# MCU.net
KiCad netlist of a schematic drawn in Altium Designer
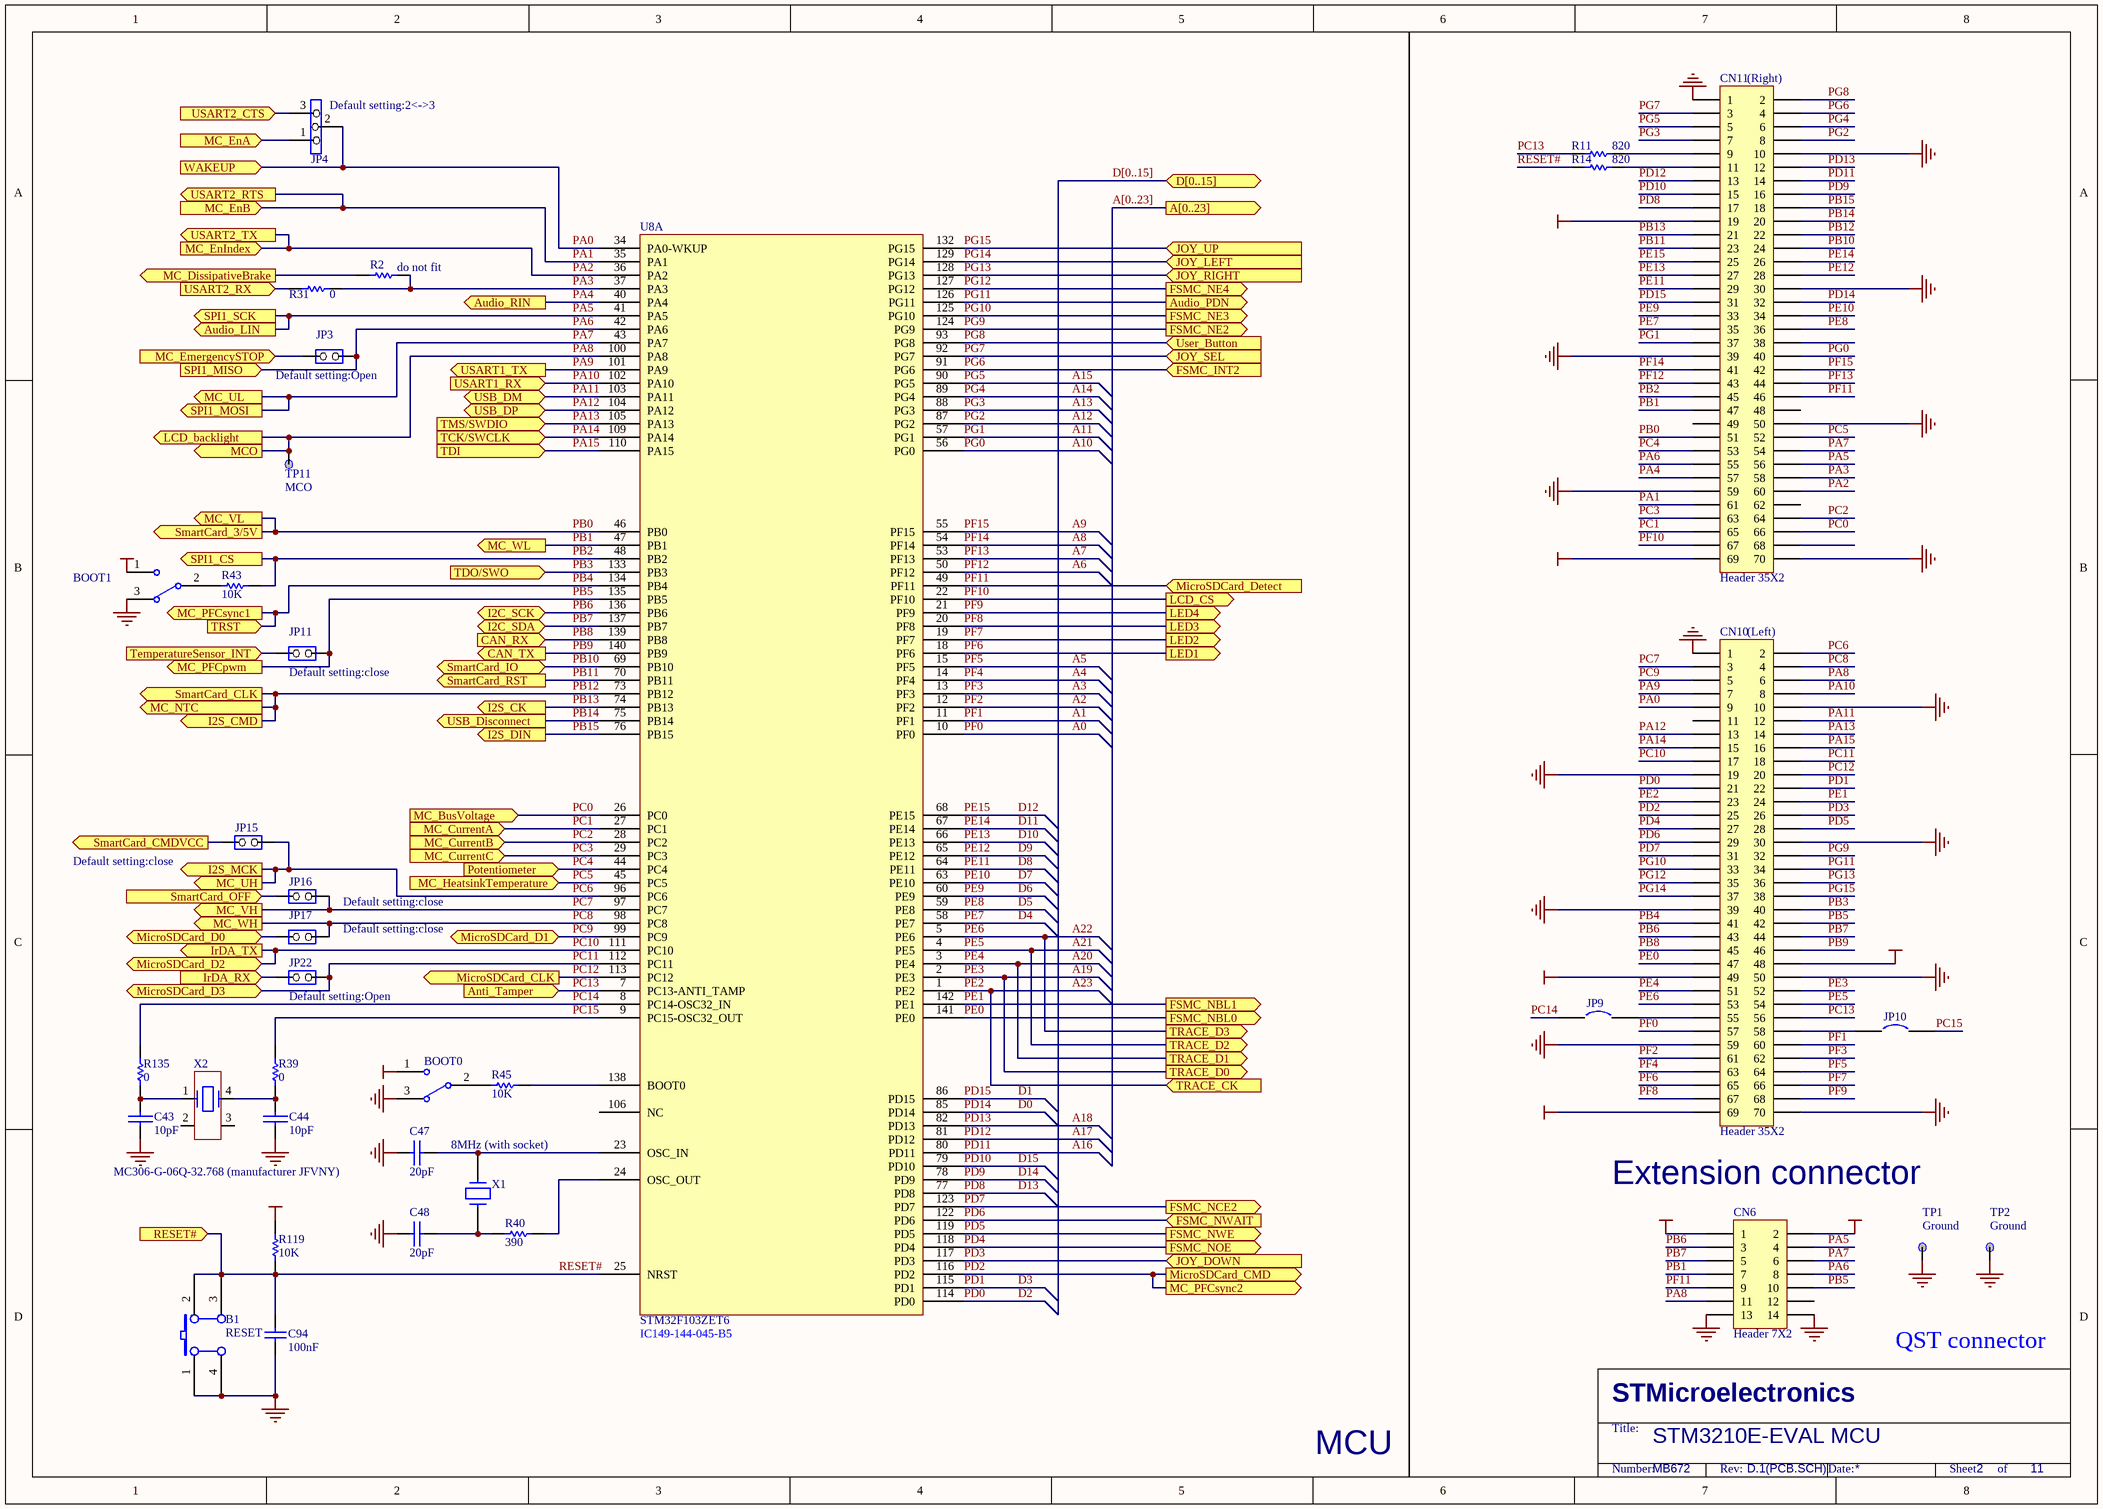
[diagram p0: MCU.SchDoc]

(export (version "E")
  (design (tool "Eeschema 10.0.6"))
  (components
    (comp (ref "B1")
      (value "RESET")
      (footprint "PB10")
      (description "SE PUSHBUTTON")
      (libsource (lib "Documents") (part "SW PUSHBUTTON"))
    )
    (comp (ref "BOOT0")
      (value "~")
      (footprint "SIP3")
      (description "SPDT Subminiature Toggle Switch, Right Angle Mounting, Vertical Actuation")
      (fields (field (name "PUBLISHER") "Altium Limited"))
      (libsource (lib "Miscellaneous Devices") (part "SW-SPDT"))
    )
    (comp (ref "BOOT1")
      (value "~")
      (footprint "SIP3")
      (description "SPDT Subminiature Toggle Switch, Right Angle Mounting, Vertical Actuation")
      (fields (field (name "PUBLISHER") "Altium Limited"))
      (libsource (lib "Miscellaneous Devices") (part "SW-SPDT"))
    )
    (comp (ref "C43")
      (value "10pF")
      (footprint "0603")
      (description "Capacitor")
      (libsource (lib "*") (part "CAP"))
    )
    (comp (ref "C44")
      (value "10pF")
      (footprint "0603")
      (description "Capacitor")
      (libsource (lib "*") (part "CAP"))
    )
    (comp (ref "C47")
      (value "20pF")
      (footprint "0603")
      (description "Capacitor")
      (libsource (lib "") (part "CAP_1"))
    )
    (comp (ref "C48")
      (value "20pF")
      (footprint "0603")
      (description "Capacitor")
      (libsource (lib "") (part "CAP_1"))
    )
    (comp (ref "C94")
      (value "100nF")
      (footprint "0603P")
      (description "Capacitor")
      (fields (field (name "PUBLISHER") "Altium Limited"))
      (libsource (lib "Miscellaneous Devices") (part "CAP"))
    )
    (comp (ref "CN6")
      (value "Header 7X2")
      (footprint "HDR2X7")
      (description "Header, 7-Pin, Dual row")
      (fields (field (name "PUBLISHER") "Altium Limited"))
      (libsource (lib "Miscellaneous Connectors") (part "Header 7X2"))
    )
    (comp (ref "CN10") (value "Header 35X2") (libsource (lib "MB672") (part "Header35X2")))
    (comp (ref "CN11") (value "Header 35X2") (libsource (lib "MB672") (part "Header35X2")))
    (comp (ref "JP3") (value "~") (footprint "SIP2") (libsource (lib "*") (part "JP2")))
    (comp (ref "JP4") (value "~") (footprint "SIP3") (libsource (lib "STR910_SCHLIB") (part "Jumper3")))
    (comp (ref "JP9")
      (value "~")
      (footprint "SPST-2")
      (description "Circuit Breaker")
      (fields (field (name "PUBLISHER") "Altium Limited"))
      (libsource (lib "Miscellaneous Devices") (part "Circuit Breaker"))
    )
    (comp (ref "JP10")
      (value "~")
      (footprint "SPST-2")
      (description "Circuit Breaker")
      (fields (field (name "PUBLISHER") "Altium Limited"))
      (libsource (lib "Miscellaneous Devices") (part "Circuit Breaker"))
    )
    (comp (ref "JP11") (value "~") (footprint "SIP2") (libsource (lib "*") (part "JP2")))
    (comp (ref "JP15") (value "~") (footprint "SIP2") (libsource (lib "*") (part "JP2")))
    (comp (ref "JP16") (value "~") (footprint "SIP2") (libsource (lib "*") (part "JP2")))
    (comp (ref "JP17") (value "~") (footprint "SIP2") (libsource (lib "*") (part "JP2")))
    (comp (ref "JP22") (value "~") (footprint "SIP2") (libsource (lib "*") (part "JP2")))
    (comp (ref "R2")
      (value "do not fit")
      (description "Resistor")
      (fields (field (name "PUBLISHER") "Altium Limited"))
      (libsource (lib "Miscellaneous Devices") (part "res1"))
    )
    (comp (ref "R11")
      (value "820")
      (description "Resistor")
      (fields (field (name "PUBLISHER") "Altium Limited"))
      (libsource (lib "Miscellaneous Devices") (part "Res1"))
    )
    (comp (ref "R14")
      (value "820")
      (description "Resistor")
      (fields (field (name "PUBLISHER") "Altium Limited"))
      (libsource (lib "Miscellaneous Devices") (part "Res1"))
    )
    (comp (ref "R31")
      (value "0")
      (description "Resistor")
      (fields (field (name "PUBLISHER") "Altium Limited"))
      (libsource (lib "Miscellaneous Devices") (part "res1"))
    )
    (comp (ref "R39")
      (value "0")
      (description "Resistor")
      (fields (field (name "PUBLISHER") "Altium Limited"))
      (libsource (lib "Miscellaneous Devices") (part "Res1"))
    )
    (comp (ref "R40")
      (value "390")
      (description "Resistor")
      (fields (field (name "PUBLISHER") "Altium Limited"))
      (libsource (lib "Miscellaneous Devices") (part "Res1"))
    )
    (comp (ref "R43")
      (value "10K")
      (description "Resistor")
      (fields (field (name "PUBLISHER") "Altium Limited"))
      (libsource (lib "Miscellaneous Devices") (part "res1"))
    )
    (comp (ref "R45")
      (value "10K")
      (description "Resistor")
      (fields (field (name "PUBLISHER") "Altium Limited"))
      (libsource (lib "Miscellaneous Devices") (part "res1"))
    )
    (comp (ref "R119")
      (value "10K")
      (footprint "0603")
      (description "Resistor")
      (fields (field (name "PUBLISHER") "Altium Limited"))
      (libsource (lib "Miscellaneous Devices") (part "res1"))
    )
    (comp (ref "R135")
      (value "0")
      (description "Resistor")
      (fields (field (name "PUBLISHER") "Altium Limited"))
      (libsource (lib "Miscellaneous Devices") (part "Res1"))
    )
    (comp (ref "TP1") (value "Ground") (footprint "TP") (libsource (lib "*") (part "TP")))
    (comp (ref "TP2") (value "Ground") (footprint "TP") (libsource (lib "*") (part "TP")))
    (comp (ref "TP11") (value "MCO") (footprint "TP") (libsource (lib "") (part "TP_1")))
    (comp (ref "U8") (value "STM32F103ZET6") (libsource (lib "MB672") (part "BigPiranha_new")))
    (comp (ref "X1")
      (value "8MHz (with socket)")
      (footprint "XTAL1")
      (description "Crystal")
      (libsource (lib "*") (part "CRYSTAL"))
    )
    (comp (ref "X2")
      (value "MC306-G-06Q-32.768 (manufacturer JFVNY)")
      (footprint "SM8")
      (libsource (lib "*") (part "MC306"))
    )
  )
  (nets
    (net (code "1") (name "+3V3") (class "Default")
      (node (ref "BOOT0") (pin "1") (pintype "passive"))
      (node (ref "BOOT1") (pin "1") (pintype "passive"))
      (node (ref "CN10") (pin "48") (pinfunction "48_48") (pintype "passive"))
      (node (ref "CN10") (pin "69") (pinfunction "69_69") (pintype "passive"))
      (node (ref "CN11") (pin "69") (pinfunction "69_69") (pintype "passive"))
      (node (ref "R119") (pin "2") (pinfunction "2_2") (pintype "passive"))
    )
    (net (code "2") (name "+5V") (class "Default")
      (node (ref "CN6") (pin "1") (pinfunction "1_1") (pintype "passive"))
      (node (ref "CN6") (pin "2") (pinfunction "2_2") (pintype "passive"))
    )
    (net (code "3") (name "/A0") (class "Default")
      (node (ref "CN10") (pin "57") (pinfunction "57_57") (pintype "passive"))
      (node (ref "U8") (pin "10") (pinfunction "PF0_10") (pintype "passive"))
    )
    (net (code "4") (name "/A1") (class "Default")
      (node (ref "CN10") (pin "60") (pinfunction "60_60") (pintype "passive"))
      (node (ref "U8") (pin "11") (pinfunction "PF1_11") (pintype "passive"))
    )
    (net (code "5") (name "/A2") (class "Default")
      (node (ref "CN10") (pin "61") (pinfunction "61_61") (pintype "passive"))
      (node (ref "U8") (pin "12") (pinfunction "PF2_12") (pintype "passive"))
    )
    (net (code "6") (name "/A3") (class "Default")
      (node (ref "CN10") (pin "62") (pinfunction "62_62") (pintype "passive"))
      (node (ref "U8") (pin "13") (pinfunction "PF3_13") (pintype "passive"))
    )
    (net (code "7") (name "/A4") (class "Default")
      (node (ref "CN10") (pin "63") (pinfunction "63_63") (pintype "passive"))
      (node (ref "U8") (pin "14") (pinfunction "PF4_14") (pintype "passive"))
    )
    (net (code "8") (name "/A5") (class "Default")
      (node (ref "CN10") (pin "64") (pinfunction "64_64") (pintype "passive"))
      (node (ref "U8") (pin "15") (pinfunction "PF5_15") (pintype "passive"))
    )
    (net (code "9") (name "/A6") (class "Default")
      (node (ref "CN11") (pin "43") (pinfunction "43_43") (pintype "passive"))
      (node (ref "U8") (pin "50") (pinfunction "PF12_50") (pintype "passive"))
    )
    (net (code "10") (name "/A7") (class "Default")
      (node (ref "CN11") (pin "44") (pinfunction "44_44") (pintype "passive"))
      (node (ref "U8") (pin "53") (pinfunction "PF13_53") (pintype "passive"))
    )
    (net (code "11") (name "/A8") (class "Default")
      (node (ref "CN11") (pin "41") (pinfunction "41_41") (pintype "passive"))
      (node (ref "U8") (pin "54") (pinfunction "PF14_54") (pintype "passive"))
    )
    (net (code "12") (name "/A9") (class "Default")
      (node (ref "CN11") (pin "42") (pinfunction "42_42") (pintype "passive"))
      (node (ref "U8") (pin "55") (pinfunction "PF15_55") (pintype "passive"))
    )
    (net (code "13") (name "/A10") (class "Default")
      (node (ref "CN11") (pin "40") (pinfunction "40_40") (pintype "passive"))
      (node (ref "U8") (pin "56") (pinfunction "PG0_56") (pintype "passive"))
    )
    (net (code "14") (name "/A11") (class "Default")
      (node (ref "CN11") (pin "37") (pinfunction "37_37") (pintype "passive"))
      (node (ref "U8") (pin "57") (pinfunction "PG1_57") (pintype "passive"))
    )
    (net (code "15") (name "/A12") (class "Default")
      (node (ref "CN11") (pin "8") (pinfunction "8_8") (pintype "passive"))
      (node (ref "U8") (pin "87") (pinfunction "PG2_87") (pintype "passive"))
    )
    (net (code "16") (name "/A13") (class "Default")
      (node (ref "CN11") (pin "7") (pinfunction "7_7") (pintype "passive"))
      (node (ref "U8") (pin "88") (pinfunction "PG3_88") (pintype "passive"))
    )
    (net (code "17") (name "/A14") (class "Default")
      (node (ref "CN11") (pin "6") (pinfunction "6_6") (pintype "passive"))
      (node (ref "U8") (pin "89") (pinfunction "PG4_89") (pintype "passive"))
    )
    (net (code "18") (name "/A15") (class "Default")
      (node (ref "CN11") (pin "5") (pinfunction "5_5") (pintype "passive"))
      (node (ref "U8") (pin "90") (pinfunction "PG5_90") (pintype "passive"))
    )
    (net (code "19") (name "/A16") (class "Default")
      (node (ref "CN11") (pin "14") (pinfunction "14_14") (pintype "passive"))
      (node (ref "U8") (pin "80") (pinfunction "PD11_80") (pintype "passive"))
    )
    (net (code "20") (name "/A17") (class "Default")
      (node (ref "CN11") (pin "13") (pinfunction "13_13") (pintype "passive"))
      (node (ref "U8") (pin "81") (pinfunction "PD12_81") (pintype "passive"))
    )
    (net (code "21") (name "/A18") (class "Default")
      (node (ref "CN11") (pin "12") (pinfunction "12_12") (pintype "passive"))
      (node (ref "U8") (pin "82") (pinfunction "PD13_82") (pintype "passive"))
    )
    (net (code "22") (name "/A19") (class "Default")
      (node (ref "CN10") (pin "52") (pinfunction "52_52") (pintype "passive"))
      (node (ref "U8") (pin "2") (pinfunction "PE3_2") (pintype "passive"))
    )
    (net (code "23") (name "/A20") (class "Default")
      (node (ref "CN10") (pin "51") (pinfunction "51_51") (pintype "passive"))
      (node (ref "U8") (pin "3") (pinfunction "PE4_3") (pintype "passive"))
    )
    (net (code "24") (name "/A21") (class "Default")
      (node (ref "CN10") (pin "54") (pinfunction "54_54") (pintype "passive"))
      (node (ref "U8") (pin "4") (pinfunction "PE5_4") (pintype "passive"))
    )
    (net (code "25") (name "/A22") (class "Default")
      (node (ref "CN10") (pin "53") (pinfunction "53_53") (pintype "passive"))
      (node (ref "U8") (pin "5") (pinfunction "PE6_5") (pintype "passive"))
    )
    (net (code "26") (name "/A23") (class "Default")
      (node (ref "CN10") (pin "23") (pinfunction "23_23") (pintype "passive"))
      (node (ref "U8") (pin "1") (pinfunction "PE2_1") (pintype "passive"))
    )
    (net (code "28") (name "/D0") (class "Default")
      (node (ref "CN11") (pin "32") (pinfunction "32_32") (pintype "passive"))
      (node (ref "U8") (pin "85") (pinfunction "PD14_85") (pintype "passive"))
    )
    (net (code "29") (name "/D1") (class "Default")
      (node (ref "CN11") (pin "31") (pinfunction "31_31") (pintype "passive"))
      (node (ref "U8") (pin "86") (pinfunction "PD15_86") (pintype "passive"))
    )
    (net (code "30") (name "/D2") (class "Default")
      (node (ref "CN10") (pin "21") (pinfunction "21_21") (pintype "passive"))
      (node (ref "U8") (pin "114") (pinfunction "PD0_114") (pintype "passive"))
    )
    (net (code "31") (name "/D3") (class "Default")
      (node (ref "CN10") (pin "22") (pinfunction "22_22") (pintype "passive"))
      (node (ref "U8") (pin "115") (pinfunction "PD1_115") (pintype "passive"))
    )
    (net (code "32") (name "/D4") (class "Default")
      (node (ref "CN11") (pin "35") (pinfunction "35_35") (pintype "passive"))
      (node (ref "U8") (pin "58") (pinfunction "PE7_58") (pintype "passive"))
    )
    (net (code "33") (name "/D5") (class "Default")
      (node (ref "CN11") (pin "36") (pinfunction "36_36") (pintype "passive"))
      (node (ref "U8") (pin "59") (pinfunction "PE8_59") (pintype "passive"))
    )
    (net (code "34") (name "/D6") (class "Default")
      (node (ref "CN11") (pin "33") (pinfunction "33_33") (pintype "passive"))
      (node (ref "U8") (pin "60") (pinfunction "PE9_60") (pintype "passive"))
    )
    (net (code "35") (name "/D7") (class "Default")
      (node (ref "CN11") (pin "34") (pinfunction "34_34") (pintype "passive"))
      (node (ref "U8") (pin "63") (pinfunction "PE10_63") (pintype "passive"))
    )
    (net (code "36") (name "/D8") (class "Default")
      (node (ref "CN11") (pin "29") (pinfunction "29_29") (pintype "passive"))
      (node (ref "U8") (pin "64") (pinfunction "PE11_64") (pintype "passive"))
    )
    (net (code "37") (name "/D9") (class "Default")
      (node (ref "CN11") (pin "28") (pinfunction "28_28") (pintype "passive"))
      (node (ref "U8") (pin "65") (pinfunction "PE12_65") (pintype "passive"))
    )
    (net (code "38") (name "/D10") (class "Default")
      (node (ref "CN11") (pin "27") (pinfunction "27_27") (pintype "passive"))
      (node (ref "U8") (pin "66") (pinfunction "PE13_66") (pintype "passive"))
    )
    (net (code "39") (name "/D11") (class "Default")
      (node (ref "CN11") (pin "26") (pinfunction "26_26") (pintype "passive"))
      (node (ref "U8") (pin "67") (pinfunction "PE14_67") (pintype "passive"))
    )
    (net (code "40") (name "/D12") (class "Default")
      (node (ref "CN11") (pin "25") (pinfunction "25_25") (pintype "passive"))
      (node (ref "U8") (pin "68") (pinfunction "PE15_68") (pintype "passive"))
    )
    (net (code "41") (name "/D13") (class "Default")
      (node (ref "CN11") (pin "17") (pinfunction "17_17") (pintype "passive"))
      (node (ref "U8") (pin "77") (pinfunction "PD8_77") (pintype "passive"))
    )
    (net (code "42") (name "/D14") (class "Default")
      (node (ref "CN11") (pin "16") (pinfunction "16_16") (pintype "passive"))
      (node (ref "U8") (pin "78") (pinfunction "PD9_78") (pintype "passive"))
    )
    (net (code "43") (name "/D15") (class "Default")
      (node (ref "CN11") (pin "15") (pinfunction "15_15") (pintype "passive"))
      (node (ref "U8") (pin "79") (pinfunction "PD10_79") (pintype "passive"))
    )
    (net (code "45") (name "/IrDA_RX") (class "Default")
      (node (ref "JP22") (pin "2") (pinfunction "NO_2") (pintype "passive"))
    )
    (net (code "46") (name "/MC_DissipativeBrake") (class "Default")
      (node (ref "R2") (pin "2") (pinfunction "2_2") (pintype "passive"))
    )
    (net (code "47") (name "/MC_EmergencySTOP") (class "Default")
      (node (ref "JP3") (pin "2") (pinfunction "NO_2") (pintype "passive"))
    )
    (net (code "48") (name "/MC_EnA") (class "Default") (node (ref "JP4") (pin "1") (pintype "passive")))
    (net (code "49") (name "/MicroSDCard_D0") (class "Default")
      (node (ref "JP17") (pin "2") (pinfunction "NO_2") (pintype "passive"))
    )
    (net (code "50") (name "/PA0") (class "Default")
      (node (ref "CN10") (pin "9") (pinfunction "9_9") (pintype "passive"))
      (node (ref "JP4") (pin "2") (pintype "passive"))
      (node (ref "U8") (pin "34") (pinfunction "PA0-WKUP_34") (pintype "passive"))
    )
    (net (code "51") (name "/PA1") (class "Default")
      (node (ref "CN11") (pin "61") (pinfunction "61_61") (pintype "passive"))
      (node (ref "U8") (pin "35") (pinfunction "PA1_35") (pintype "passive"))
    )
    (net (code "52") (name "/PA2") (class "Default")
      (node (ref "CN11") (pin "60") (pinfunction "60_60") (pintype "passive"))
      (node (ref "U8") (pin "36") (pinfunction "PA2_36") (pintype "passive"))
    )
    (net (code "53") (name "/PA3") (class "Default")
      (node (ref "CN11") (pin "58") (pinfunction "58_58") (pintype "passive"))
      (node (ref "R2") (pin "1") (pinfunction "1_1") (pintype "passive"))
      (node (ref "R31") (pin "1") (pinfunction "1_1") (pintype "passive"))
      (node (ref "U8") (pin "37") (pinfunction "PA3_37") (pintype "passive"))
    )
    (net (code "54") (name "/PA4") (class "Default")
      (node (ref "CN11") (pin "57") (pinfunction "57_57") (pintype "passive"))
      (node (ref "U8") (pin "40") (pinfunction "PA4_40") (pintype "passive"))
    )
    (net (code "55") (name "/PA5") (class "Default")
      (node (ref "CN11") (pin "56") (pinfunction "56_56") (pintype "passive"))
      (node (ref "CN6") (pin "4") (pinfunction "4_4") (pintype "passive"))
      (node (ref "U8") (pin "41") (pinfunction "PA5_41") (pintype "passive"))
    )
    (net (code "56") (name "/PA6") (class "Default")
      (node (ref "CN11") (pin "55") (pinfunction "55_55") (pintype "passive"))
      (node (ref "CN6") (pin "8") (pinfunction "8_8") (pintype "passive"))
      (node (ref "JP3") (pin "1") (pinfunction "COMMON_1") (pintype "passive"))
      (node (ref "U8") (pin "42") (pinfunction "PA6_42") (pintype "passive"))
    )
    (net (code "57") (name "/PA7") (class "Default")
      (node (ref "CN11") (pin "54") (pinfunction "54_54") (pintype "passive"))
      (node (ref "CN6") (pin "6") (pinfunction "6_6") (pintype "passive"))
      (node (ref "U8") (pin "43") (pinfunction "PA7_43") (pintype "passive"))
    )
    (net (code "58") (name "/PA8") (class "Default")
      (node (ref "CN10") (pin "6") (pinfunction "6_6") (pintype "passive"))
      (node (ref "CN6") (pin "11") (pinfunction "11_11") (pintype "passive"))
      (node (ref "TP11") (pin "1") (pinfunction "1_1") (pintype "passive"))
      (node (ref "U8") (pin "100") (pinfunction "PA8_100") (pintype "passive"))
    )
    (net (code "59") (name "/PA9") (class "Default")
      (node (ref "CN10") (pin "7") (pinfunction "7_7") (pintype "passive"))
      (node (ref "U8") (pin "101") (pinfunction "PA9_101") (pintype "passive"))
    )
    (net (code "60") (name "/PA10") (class "Default")
      (node (ref "CN10") (pin "8") (pinfunction "8_8") (pintype "passive"))
      (node (ref "U8") (pin "102") (pinfunction "PA10_102") (pintype "passive"))
    )
    (net (code "61") (name "/PA11") (class "Default")
      (node (ref "CN10") (pin "12") (pinfunction "12_12") (pintype "passive"))
      (node (ref "U8") (pin "103") (pinfunction "PA11_103") (pintype "passive"))
    )
    (net (code "62") (name "/PA12") (class "Default")
      (node (ref "CN10") (pin "13") (pinfunction "13_13") (pintype "passive"))
      (node (ref "U8") (pin "104") (pinfunction "PA12_104") (pintype "passive"))
    )
    (net (code "63") (name "/PA13") (class "Default")
      (node (ref "CN10") (pin "14") (pinfunction "14_14") (pintype "passive"))
      (node (ref "U8") (pin "105") (pinfunction "PA13_105") (pintype "passive"))
    )
    (net (code "64") (name "/PA14") (class "Default")
      (node (ref "CN10") (pin "15") (pinfunction "15_15") (pintype "passive"))
      (node (ref "U8") (pin "109") (pinfunction "PA14_109") (pintype "passive"))
    )
    (net (code "65") (name "/PA15") (class "Default")
      (node (ref "CN10") (pin "16") (pinfunction "16_16") (pintype "passive"))
      (node (ref "U8") (pin "110") (pinfunction "PA15_110") (pintype "passive"))
    )
    (net (code "66") (name "/PB0") (class "Default")
      (node (ref "CN11") (pin "51") (pinfunction "51_51") (pintype "passive"))
      (node (ref "U8") (pin "46") (pinfunction "PB0_46") (pintype "passive"))
    )
    (net (code "67") (name "/PB1") (class "Default")
      (node (ref "CN11") (pin "47") (pinfunction "47_47") (pintype "passive"))
      (node (ref "CN6") (pin "7") (pinfunction "7_7") (pintype "passive"))
      (node (ref "U8") (pin "47") (pinfunction "PB1_47") (pintype "passive"))
    )
    (net (code "68") (name "/PB2") (class "Default")
      (node (ref "CN11") (pin "45") (pinfunction "45_45") (pintype "passive"))
      (node (ref "R43") (pin "1") (pinfunction "1_1") (pintype "passive"))
      (node (ref "U8") (pin "48") (pinfunction "PB2_48") (pintype "passive"))
    )
    (net (code "69") (name "/PB3") (class "Default")
      (node (ref "CN10") (pin "40") (pinfunction "40_40") (pintype "passive"))
      (node (ref "U8") (pin "133") (pinfunction "PB3_133") (pintype "passive"))
    )
    (net (code "70") (name "/PB4") (class "Default")
      (node (ref "CN10") (pin "41") (pinfunction "41_41") (pintype "passive"))
      (node (ref "U8") (pin "134") (pinfunction "PB4_134") (pintype "passive"))
    )
    (net (code "71") (name "/PB5") (class "Default")
      (node (ref "CN10") (pin "42") (pinfunction "42_42") (pintype "passive"))
      (node (ref "CN6") (pin "10") (pinfunction "10_10") (pintype "passive"))
      (node (ref "JP11") (pin "1") (pinfunction "COMMON_1") (pintype "passive"))
      (node (ref "U8") (pin "135") (pinfunction "PB5_135") (pintype "passive"))
    )
    (net (code "72") (name "/PB6") (class "Default")
      (node (ref "CN10") (pin "43") (pinfunction "43_43") (pintype "passive"))
      (node (ref "CN6") (pin "3") (pinfunction "3_3") (pintype "passive"))
      (node (ref "U8") (pin "136") (pinfunction "PB6_136") (pintype "passive"))
    )
    (net (code "73") (name "/PB7") (class "Default")
      (node (ref "CN10") (pin "44") (pinfunction "44_44") (pintype "passive"))
      (node (ref "CN6") (pin "5") (pinfunction "5_5") (pintype "passive"))
      (node (ref "U8") (pin "137") (pinfunction "PB7_137") (pintype "passive"))
    )
    (net (code "74") (name "/PB8") (class "Default")
      (node (ref "CN10") (pin "45") (pinfunction "45_45") (pintype "passive"))
      (node (ref "U8") (pin "139") (pinfunction "PB8_139") (pintype "passive"))
    )
    (net (code "75") (name "/PB9") (class "Default")
      (node (ref "CN10") (pin "46") (pinfunction "46_46") (pintype "passive"))
      (node (ref "U8") (pin "140") (pinfunction "PB9_140") (pintype "passive"))
    )
    (net (code "76") (name "/PB10") (class "Default")
      (node (ref "CN11") (pin "24") (pinfunction "24_24") (pintype "passive"))
      (node (ref "U8") (pin "69") (pinfunction "PB10_69") (pintype "passive"))
    )
    (net (code "77") (name "/PB11") (class "Default")
      (node (ref "CN11") (pin "23") (pinfunction "23_23") (pintype "passive"))
      (node (ref "U8") (pin "70") (pinfunction "PB11_70") (pintype "passive"))
    )
    (net (code "78") (name "/PB12") (class "Default")
      (node (ref "CN11") (pin "22") (pinfunction "22_22") (pintype "passive"))
      (node (ref "U8") (pin "73") (pinfunction "PB12_73") (pintype "passive"))
    )
    (net (code "79") (name "/PB13") (class "Default")
      (node (ref "CN11") (pin "21") (pinfunction "21_21") (pintype "passive"))
      (node (ref "U8") (pin "74") (pinfunction "PB13_74") (pintype "passive"))
    )
    (net (code "80") (name "/PB14") (class "Default")
      (node (ref "CN11") (pin "20") (pinfunction "20_20") (pintype "passive"))
      (node (ref "U8") (pin "75") (pinfunction "PB14_75") (pintype "passive"))
    )
    (net (code "81") (name "/PB15") (class "Default")
      (node (ref "CN11") (pin "18") (pinfunction "18_18") (pintype "passive"))
      (node (ref "U8") (pin "76") (pinfunction "PB15_76") (pintype "passive"))
    )
    (net (code "82") (name "/PC0") (class "Default")
      (node (ref "CN11") (pin "66") (pinfunction "66_66") (pintype "passive"))
      (node (ref "U8") (pin "26") (pinfunction "PC0_26") (pintype "passive"))
    )
    (net (code "83") (name "/PC1") (class "Default")
      (node (ref "CN11") (pin "65") (pinfunction "65_65") (pintype "passive"))
      (node (ref "U8") (pin "27") (pinfunction "PC1_27") (pintype "passive"))
    )
    (net (code "84") (name "/PC2") (class "Default")
      (node (ref "CN11") (pin "64") (pinfunction "64_64") (pintype "passive"))
      (node (ref "U8") (pin "28") (pinfunction "PC2_28") (pintype "passive"))
    )
    (net (code "85") (name "/PC3") (class "Default")
      (node (ref "CN11") (pin "63") (pinfunction "63_63") (pintype "passive"))
      (node (ref "U8") (pin "29") (pinfunction "PC3_29") (pintype "passive"))
    )
    (net (code "86") (name "/PC4") (class "Default")
      (node (ref "CN11") (pin "53") (pinfunction "53_53") (pintype "passive"))
      (node (ref "U8") (pin "44") (pinfunction "PC4_44") (pintype "passive"))
    )
    (net (code "87") (name "/PC5") (class "Default")
      (node (ref "CN11") (pin "52") (pinfunction "52_52") (pintype "passive"))
      (node (ref "U8") (pin "45") (pinfunction "PC5_45") (pintype "passive"))
    )
    (net (code "88") (name "/PC6") (class "Default")
      (node (ref "CN10") (pin "2") (pinfunction "2_2") (pintype "passive"))
      (node (ref "JP15") (pin "1") (pinfunction "COMMON_1") (pintype "passive"))
      (node (ref "U8") (pin "96") (pinfunction "PC6_96") (pintype "passive"))
    )
    (net (code "89") (name "/PC7") (class "Default")
      (node (ref "CN10") (pin "3") (pinfunction "3_3") (pintype "passive"))
      (node (ref "JP16") (pin "1") (pinfunction "COMMON_1") (pintype "passive"))
      (node (ref "U8") (pin "97") (pinfunction "PC7_97") (pintype "passive"))
    )
    (net (code "90") (name "/PC8") (class "Default")
      (node (ref "CN10") (pin "4") (pinfunction "4_4") (pintype "passive"))
      (node (ref "JP17") (pin "1") (pinfunction "COMMON_1") (pintype "passive"))
      (node (ref "U8") (pin "98") (pinfunction "PC8_98") (pintype "passive"))
    )
    (net (code "91") (name "/PC9") (class "Default")
      (node (ref "CN10") (pin "5") (pinfunction "5_5") (pintype "passive"))
      (node (ref "U8") (pin "99") (pinfunction "PC9_99") (pintype "passive"))
    )
    (net (code "92") (name "/PC10") (class "Default")
      (node (ref "CN10") (pin "17") (pinfunction "17_17") (pintype "passive"))
      (node (ref "U8") (pin "111") (pinfunction "PC10_111") (pintype "passive"))
    )
    (net (code "93") (name "/PC11") (class "Default")
      (node (ref "CN10") (pin "18") (pinfunction "18_18") (pintype "passive"))
      (node (ref "JP22") (pin "1") (pinfunction "COMMON_1") (pintype "passive"))
      (node (ref "U8") (pin "112") (pinfunction "PC11_112") (pintype "passive"))
    )
    (net (code "94") (name "/PC12") (class "Default")
      (node (ref "CN10") (pin "20") (pinfunction "20_20") (pintype "passive"))
      (node (ref "U8") (pin "113") (pinfunction "PC12_113") (pintype "passive"))
    )
    (net (code "95") (name "/PC13") (class "Default")
      (node (ref "CN10") (pin "56") (pinfunction "56_56") (pintype "passive"))
      (node (ref "R11") (pin "1") (pinfunction "1_1") (pintype "passive"))
      (node (ref "U8") (pin "7") (pinfunction "PC13-ANTI_TAMP_7") (pintype "passive"))
    )
    (net (code "96") (name "/PC14") (class "Default")
      (node (ref "JP9") (pin "1") (pinfunction "1_1") (pintype "passive"))
      (node (ref "R135") (pin "2") (pinfunction "2_2") (pintype "passive"))
      (node (ref "U8") (pin "8") (pinfunction "PC14-OSC32_IN_8") (pintype "passive"))
    )
    (net (code "97") (name "/PC15") (class "Default")
      (node (ref "JP10") (pin "2") (pinfunction "2_2") (pintype "passive"))
      (node (ref "R39") (pin "2") (pinfunction "2_2") (pintype "passive"))
      (node (ref "U8") (pin "9") (pinfunction "PC15-OSC32_OUT_9") (pintype "passive"))
    )
    (net (code "98") (name "/PD2") (class "Default")
      (node (ref "CN10") (pin "25") (pinfunction "25_25") (pintype "passive"))
      (node (ref "U8") (pin "116") (pinfunction "PD2_116") (pintype "passive"))
    )
    (net (code "99") (name "/PD3") (class "Default")
      (node (ref "CN10") (pin "26") (pinfunction "26_26") (pintype "passive"))
      (node (ref "U8") (pin "117") (pinfunction "PD3_117") (pintype "passive"))
    )
    (net (code "100") (name "/PD4") (class "Default")
      (node (ref "CN10") (pin "27") (pinfunction "27_27") (pintype "passive"))
      (node (ref "U8") (pin "118") (pinfunction "PD4_118") (pintype "passive"))
    )
    (net (code "101") (name "/PD5") (class "Default")
      (node (ref "CN10") (pin "28") (pinfunction "28_28") (pintype "passive"))
      (node (ref "U8") (pin "119") (pinfunction "PD5_119") (pintype "passive"))
    )
    (net (code "102") (name "/PD6") (class "Default")
      (node (ref "CN10") (pin "29") (pinfunction "29_29") (pintype "passive"))
      (node (ref "U8") (pin "122") (pinfunction "PD6_122") (pintype "passive"))
    )
    (net (code "103") (name "/PD7") (class "Default")
      (node (ref "CN10") (pin "31") (pinfunction "31_31") (pintype "passive"))
      (node (ref "U8") (pin "123") (pinfunction "PD7_123") (pintype "passive"))
    )
    (net (code "104") (name "/PE0") (class "Default")
      (node (ref "CN10") (pin "47") (pinfunction "47_47") (pintype "passive"))
      (node (ref "U8") (pin "141") (pinfunction "PE0_141") (pintype "passive"))
    )
    (net (code "105") (name "/PE1") (class "Default")
      (node (ref "CN10") (pin "24") (pinfunction "24_24") (pintype "passive"))
      (node (ref "U8") (pin "142") (pinfunction "PE1_142") (pintype "passive"))
    )
    (net (code "106") (name "/PF6") (class "Default")
      (node (ref "CN10") (pin "65") (pinfunction "65_65") (pintype "passive"))
      (node (ref "U8") (pin "18") (pinfunction "PF6_18") (pintype "passive"))
    )
    (net (code "107") (name "/PF7") (class "Default")
      (node (ref "CN10") (pin "66") (pinfunction "66_66") (pintype "passive"))
      (node (ref "U8") (pin "19") (pinfunction "PF7_19") (pintype "passive"))
    )
    (net (code "108") (name "/PF8") (class "Default")
      (node (ref "CN10") (pin "67") (pinfunction "67_67") (pintype "passive"))
      (node (ref "U8") (pin "20") (pinfunction "PF8_20") (pintype "passive"))
    )
    (net (code "109") (name "/PF9") (class "Default")
      (node (ref "CN10") (pin "68") (pinfunction "68_68") (pintype "passive"))
      (node (ref "U8") (pin "21") (pinfunction "PF9_21") (pintype "passive"))
    )
    (net (code "110") (name "/PF10") (class "Default")
      (node (ref "CN11") (pin "67") (pinfunction "67_67") (pintype "passive"))
      (node (ref "U8") (pin "22") (pinfunction "PF10_22") (pintype "passive"))
    )
    (net (code "111") (name "/PF11") (class "Default")
      (node (ref "CN11") (pin "46") (pinfunction "46_46") (pintype "passive"))
      (node (ref "CN6") (pin "9") (pinfunction "9_9") (pintype "passive"))
      (node (ref "U8") (pin "49") (pinfunction "PF11_49") (pintype "passive"))
    )
    (net (code "112") (name "/PG6") (class "Default")
      (node (ref "CN11") (pin "4") (pinfunction "4_4") (pintype "passive"))
      (node (ref "U8") (pin "91") (pinfunction "PG6_91") (pintype "passive"))
    )
    (net (code "113") (name "/PG7") (class "Default")
      (node (ref "CN11") (pin "3") (pinfunction "3_3") (pintype "passive"))
      (node (ref "U8") (pin "92") (pinfunction "PG7_92") (pintype "passive"))
    )
    (net (code "114") (name "/PG8") (class "Default")
      (node (ref "CN11") (pin "2") (pinfunction "2_2") (pintype "passive"))
      (node (ref "U8") (pin "93") (pinfunction "PG8_93") (pintype "passive"))
    )
    (net (code "115") (name "/PG9") (class "Default")
      (node (ref "CN10") (pin "32") (pinfunction "32_32") (pintype "passive"))
      (node (ref "U8") (pin "124") (pinfunction "PG9_124") (pintype "passive"))
    )
    (net (code "116") (name "/PG10") (class "Default")
      (node (ref "CN10") (pin "33") (pinfunction "33_33") (pintype "passive"))
      (node (ref "U8") (pin "125") (pinfunction "PG10_125") (pintype "passive"))
    )
    (net (code "117") (name "/PG11") (class "Default")
      (node (ref "CN10") (pin "34") (pinfunction "34_34") (pintype "passive"))
      (node (ref "U8") (pin "126") (pinfunction "PG11_126") (pintype "passive"))
    )
    (net (code "118") (name "/PG12") (class "Default")
      (node (ref "CN10") (pin "35") (pinfunction "35_35") (pintype "passive"))
      (node (ref "U8") (pin "127") (pinfunction "PG12_127") (pintype "passive"))
    )
    (net (code "119") (name "/PG13") (class "Default")
      (node (ref "CN10") (pin "36") (pinfunction "36_36") (pintype "passive"))
      (node (ref "U8") (pin "128") (pinfunction "PG13_128") (pintype "passive"))
    )
    (net (code "120") (name "/PG14") (class "Default")
      (node (ref "CN10") (pin "37") (pinfunction "37_37") (pintype "passive"))
      (node (ref "U8") (pin "129") (pinfunction "PG14_129") (pintype "passive"))
    )
    (net (code "121") (name "/PG15") (class "Default")
      (node (ref "CN10") (pin "38") (pinfunction "38_38") (pintype "passive"))
      (node (ref "U8") (pin "132") (pinfunction "PG15_132") (pintype "passive"))
    )
    (net (code "122") (name "/RESET#") (class "Default")
      (node (ref "B1") (pin "2") (pinfunction "B0_2") (pintype "passive"))
      (node (ref "B1") (pin "3") (pinfunction "B1_3") (pintype "passive"))
      (node (ref "C94") (pin "2") (pinfunction "2_2") (pintype "passive"))
      (node (ref "R119") (pin "1") (pinfunction "1_1") (pintype "passive"))
      (node (ref "R14") (pin "2") (pinfunction "2_2") (pintype "passive"))
      (node (ref "U8") (pin "25") (pinfunction "NRST_25") (pintype "passive"))
    )
    (net (code "123") (name "/SmartCard_CMDVCC") (class "Default")
      (node (ref "JP15") (pin "2") (pinfunction "NO_2") (pintype "passive"))
    )
    (net (code "124") (name "/SmartCard_OFF") (class "Default")
      (node (ref "JP16") (pin "2") (pinfunction "NO_2") (pintype "passive"))
    )
    (net (code "125") (name "/TemperatureSensor_INT") (class "Default")
      (node (ref "JP11") (pin "2") (pinfunction "NO_2") (pintype "passive"))
    )
    (net (code "126") (name "/USART2_CTS") (class "Default") (node (ref "JP4") (pin "3") (pintype "passive")))
    (net (code "127") (name "/USART2_RX") (class "Default")
      (node (ref "R31") (pin "2") (pinfunction "2_2") (pintype "passive"))
    )
    (net (code "128") (name "D5V") (class "Default")
      (node (ref "CN10") (pin "49") (pinfunction "49_49") (pintype "passive"))
      (node (ref "CN11") (pin "19") (pinfunction "19_19") (pintype "passive"))
    )
    (net (code "129") (name "GND") (class "Default")
      (node (ref "B1") (pin "1") (pinfunction "A0_1") (pintype "passive"))
      (node (ref "B1") (pin "4") (pinfunction "A1_4") (pintype "passive"))
      (node (ref "BOOT0") (pin "3") (pintype "passive"))
      (node (ref "BOOT1") (pin "3") (pintype "passive"))
      (node (ref "C43") (pin "2") (pinfunction "2_2") (pintype "passive"))
      (node (ref "C44") (pin "2") (pinfunction "2_2") (pintype "passive"))
      (node (ref "C47") (pin "2") (pinfunction "2_2") (pintype "passive"))
      (node (ref "C48") (pin "2") (pinfunction "2_2") (pintype "passive"))
      (node (ref "C94") (pin "1") (pinfunction "1_1") (pintype "passive"))
      (node (ref "CN10") (pin "1") (pinfunction "1_1") (pintype "passive"))
      (node (ref "CN10") (pin "10") (pinfunction "10_10") (pintype "passive"))
      (node (ref "CN10") (pin "19") (pinfunction "19_19") (pintype "passive"))
      (node (ref "CN10") (pin "30") (pinfunction "30_30") (pintype "passive"))
      (node (ref "CN10") (pin "39") (pinfunction "39_39") (pintype "passive"))
      (node (ref "CN10") (pin "50") (pinfunction "50_50") (pintype "passive"))
      (node (ref "CN10") (pin "59") (pinfunction "59_59") (pintype "passive"))
      (node (ref "CN10") (pin "70") (pinfunction "70_70") (pintype "passive"))
      (node (ref "CN11") (pin "1") (pinfunction "1_1") (pintype "passive"))
      (node (ref "CN11") (pin "10") (pinfunction "10_10") (pintype "passive"))
      (node (ref "CN11") (pin "30") (pinfunction "30_30") (pintype "passive"))
      (node (ref "CN11") (pin "39") (pinfunction "39_39") (pintype "passive"))
      (node (ref "CN11") (pin "50") (pinfunction "50_50") (pintype "passive"))
      (node (ref "CN11") (pin "59") (pinfunction "59_59") (pintype "passive"))
      (node (ref "CN11") (pin "70") (pinfunction "70_70") (pintype "passive"))
      (node (ref "CN6") (pin "13") (pinfunction "13_13") (pintype "passive"))
      (node (ref "CN6") (pin "14") (pinfunction "14_14") (pintype "passive"))
      (node (ref "TP1") (pin "1") (pinfunction "1_1") (pintype "passive"))
      (node (ref "TP2") (pin "1") (pinfunction "1_1") (pintype "passive"))
    )
    (net (code "130") (name "Net-(BOOT0-Pad2)") (class "Default")
      (node (ref "BOOT0") (pin "2") (pintype "passive"))
      (node (ref "R45") (pin "2") (pinfunction "2_2") (pintype "passive"))
    )
    (net (code "131") (name "Net-(BOOT1-Pad2)") (class "Default")
      (node (ref "BOOT1") (pin "2") (pintype "passive"))
      (node (ref "R43") (pin "2") (pinfunction "2_2") (pintype "passive"))
    )
    (net (code "132") (name "Net-(C43-Pad1)") (class "Default")
      (node (ref "C43") (pin "1") (pinfunction "1_1") (pintype "passive"))
      (node (ref "R135") (pin "1") (pinfunction "1_1") (pintype "passive"))
      (node (ref "X2") (pin "1") (pinfunction "1_1") (pintype "passive"))
    )
    (net (code "133") (name "Net-(C44-Pad1)") (class "Default")
      (node (ref "C44") (pin "1") (pinfunction "1_1") (pintype "passive"))
      (node (ref "R39") (pin "1") (pinfunction "1_1") (pintype "passive"))
      (node (ref "X2") (pin "4") (pinfunction "4_4") (pintype "passive"))
    )
    (net (code "134") (name "Net-(C48-Pad1)") (class "Default")
      (node (ref "C48") (pin "1") (pinfunction "1_1") (pintype "passive"))
      (node (ref "R40") (pin "2") (pinfunction "2_2") (pintype "passive"))
      (node (ref "X1") (pin "1") (pinfunction "1_1") (pintype "passive"))
    )
    (net (code "135") (name "Net-(CN10-Pad55)") (class "Default")
      (node (ref "CN10") (pin "55") (pinfunction "55_55") (pintype "passive"))
      (node (ref "JP9") (pin "2") (pinfunction "2_2") (pintype "passive"))
    )
    (net (code "136") (name "Net-(CN10-Pad58)") (class "Default")
      (node (ref "CN10") (pin "58") (pinfunction "58_58") (pintype "passive"))
      (node (ref "JP10") (pin "1") (pinfunction "1_1") (pintype "passive"))
    )
    (net (code "137") (name "Net-(CN11-Pad9)") (class "Default")
      (node (ref "CN11") (pin "9") (pinfunction "9_9") (pintype "passive"))
      (node (ref "R11") (pin "2") (pinfunction "2_2") (pintype "passive"))
    )
    (net (code "138") (name "Net-(CN11-Pad11)") (class "Default")
      (node (ref "CN11") (pin "11") (pinfunction "11_11") (pintype "passive"))
      (node (ref "R14") (pin "1") (pinfunction "1_1") (pintype "passive"))
    )
    (net (code "139") (name "Net-(U8A-BOOT0)") (class "Default")
      (node (ref "R45") (pin "1") (pinfunction "1_1") (pintype "passive"))
      (node (ref "U8") (pin "138") (pinfunction "BOOT0_138") (pintype "passive"))
    )
    (net (code "140") (name "Net-(U8A-OSC_IN)") (class "Default")
      (node (ref "C47") (pin "1") (pinfunction "1_1") (pintype "passive"))
      (node (ref "U8") (pin "23") (pinfunction "OSC_IN_23") (pintype "passive"))
      (node (ref "X1") (pin "2") (pinfunction "2_2") (pintype "passive"))
    )
    (net (code "141") (name "Net-(U8A-OSC_OUT)") (class "Default")
      (node (ref "R40") (pin "1") (pinfunction "1_1") (pintype "passive"))
      (node (ref "U8") (pin "24") (pinfunction "OSC_OUT_24") (pintype "passive"))
    )
    (net (code "142") (name "unconnected-(CN6-Pad12)") (class "Default")
      (node (ref "CN6") (pin "12") (pinfunction "12_12") (pintype "passive"))
    )
    (net (code "143") (name "unconnected-(CN10-Pad11)") (class "Default")
      (node (ref "CN10") (pin "11") (pinfunction "11_11") (pintype "passive"))
    )
    (net (code "144") (name "unconnected-(CN11-Pad38)") (class "Default")
      (node (ref "CN11") (pin "38") (pinfunction "38_38") (pintype "passive"))
    )
    (net (code "145") (name "unconnected-(CN11-Pad48)") (class "Default")
      (node (ref "CN11") (pin "48") (pinfunction "48_48") (pintype "passive"))
    )
    (net (code "146") (name "unconnected-(CN11-Pad49)") (class "Default")
      (node (ref "CN11") (pin "49") (pinfunction "49_49") (pintype "passive"))
    )
    (net (code "147") (name "unconnected-(CN11-Pad62)") (class "Default")
      (node (ref "CN11") (pin "62") (pinfunction "62_62") (pintype "passive"))
    )
    (net (code "148") (name "unconnected-(CN11-Pad68)") (class "Default")
      (node (ref "CN11") (pin "68") (pinfunction "68_68") (pintype "passive"))
    )
    (net (code "149") (name "unconnected-(U8A-NC-Pad106)") (class "Default")
      (node (ref "U8") (pin "106") (pinfunction "NC_106") (pintype "passive"))
    )
    (net (code "150") (name "unconnected-(X2-Pad2)") (class "Default")
      (node (ref "X2") (pin "2") (pinfunction "2_2") (pintype "passive"))
    )
    (net (code "151") (name "unconnected-(X2-Pad3)") (class "Default")
      (node (ref "X2") (pin "3") (pinfunction "3_3") (pintype "passive"))
    )
  )
)
